# birth1_brd2.net
KiCad netlist of a schematic drawn in EAGLE
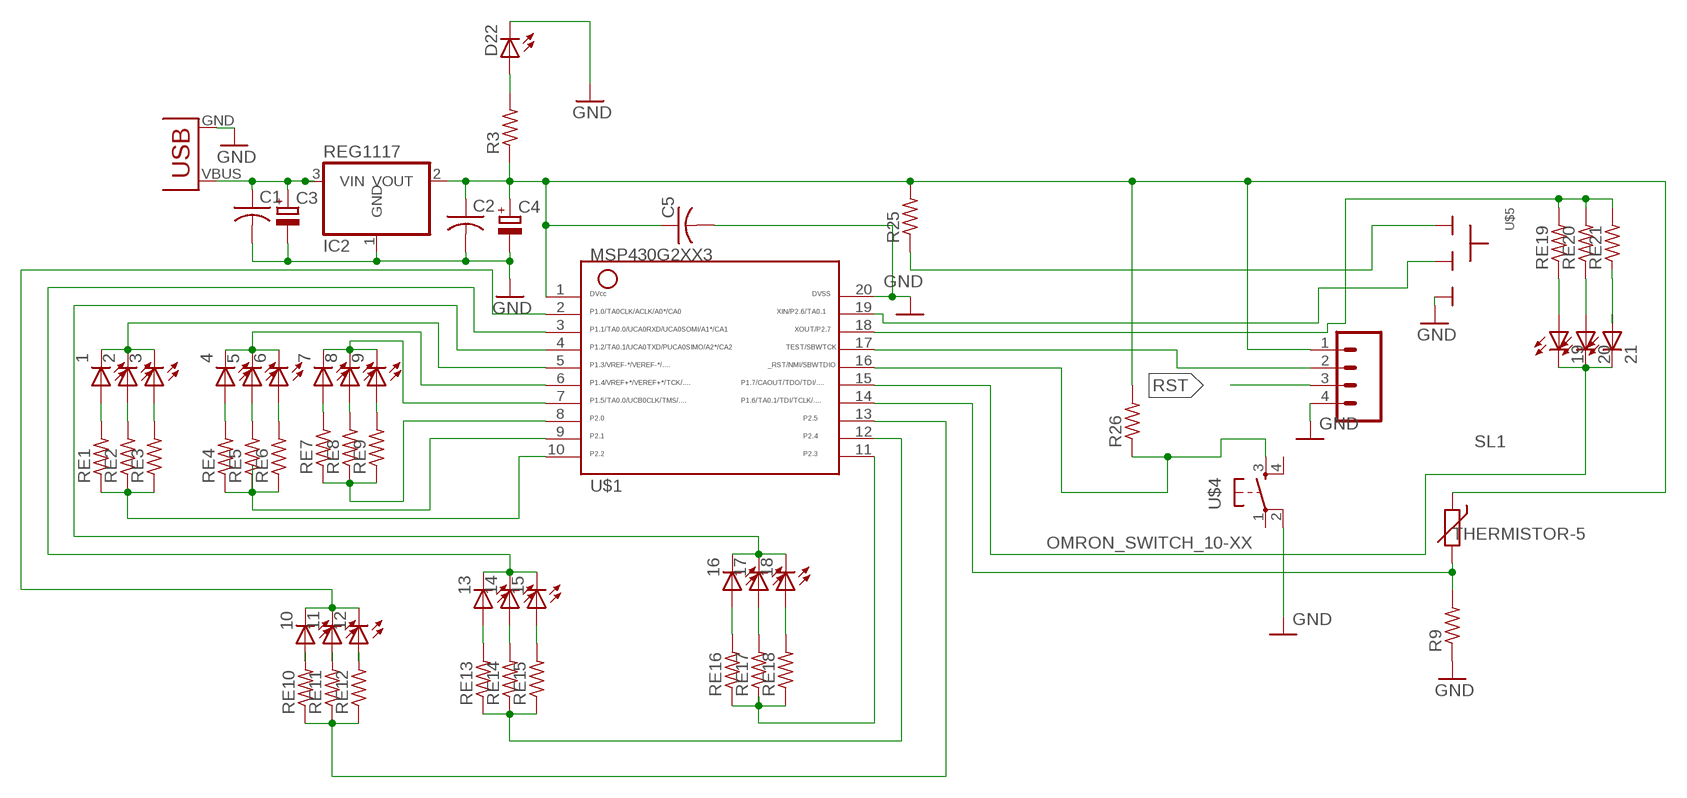
[diagram p0: schematic, sheet 1]

(export (version "E")
  (design (tool "Eeschema 10.0.6"))
  (components
    (comp (ref "1")
      (value "LED3MM")
      (footprint "eagle-import:LED3MM")
      (libsource (lib "eagle-import") (part "LED3MM"))
    )
    (comp (ref "2")
      (value "LED3MM")
      (footprint "eagle-import:LED3MM")
      (libsource (lib "eagle-import") (part "LED3MM"))
    )
    (comp (ref "3")
      (value "LED3MM")
      (footprint "eagle-import:LED3MM")
      (libsource (lib "eagle-import") (part "LED3MM"))
    )
    (comp (ref "4")
      (value "LED3MM")
      (footprint "eagle-import:LED3MM")
      (libsource (lib "eagle-import") (part "LED3MM"))
    )
    (comp (ref "5")
      (value "LED3MM")
      (footprint "eagle-import:LED3MM")
      (libsource (lib "eagle-import") (part "LED3MM"))
    )
    (comp (ref "6")
      (value "LED3MM")
      (footprint "eagle-import:LED3MM")
      (libsource (lib "eagle-import") (part "LED3MM"))
    )
    (comp (ref "7")
      (value "LED3MM")
      (footprint "eagle-import:LED3MM")
      (libsource (lib "eagle-import") (part "LED3MM"))
    )
    (comp (ref "8")
      (value "LED3MM")
      (footprint "eagle-import:LED3MM")
      (libsource (lib "eagle-import") (part "LED3MM"))
    )
    (comp (ref "9")
      (value "LED3MM")
      (footprint "eagle-import:LED3MM")
      (libsource (lib "eagle-import") (part "LED3MM"))
    )
    (comp (ref "10")
      (value "LED3MM")
      (footprint "eagle-import:LED3MM")
      (libsource (lib "eagle-import") (part "LED3MM"))
    )
    (comp (ref "11")
      (value "LED3MM")
      (footprint "eagle-import:LED3MM")
      (libsource (lib "eagle-import") (part "LED3MM"))
    )
    (comp (ref "12")
      (value "LED3MM")
      (footprint "eagle-import:LED3MM")
      (libsource (lib "eagle-import") (part "LED3MM"))
    )
    (comp (ref "13")
      (value "LED3MM")
      (footprint "eagle-import:LED3MM")
      (libsource (lib "eagle-import") (part "LED3MM"))
    )
    (comp (ref "14")
      (value "LED3MM")
      (footprint "eagle-import:LED3MM")
      (libsource (lib "eagle-import") (part "LED3MM"))
    )
    (comp (ref "15")
      (value "LED3MM")
      (footprint "eagle-import:LED3MM")
      (libsource (lib "eagle-import") (part "LED3MM"))
    )
    (comp (ref "16")
      (value "LED3MM")
      (footprint "eagle-import:LED3MM")
      (libsource (lib "eagle-import") (part "LED3MM"))
    )
    (comp (ref "17")
      (value "LED3MM")
      (footprint "eagle-import:LED3MM")
      (libsource (lib "eagle-import") (part "LED3MM"))
    )
    (comp (ref "18")
      (value "LED3MM")
      (footprint "eagle-import:LED3MM")
      (libsource (lib "eagle-import") (part "LED3MM"))
    )
    (comp (ref "19")
      (value "LED3MM")
      (footprint "eagle-import:LED3MM")
      (libsource (lib "eagle-import") (part "LED3MM"))
    )
    (comp (ref "20")
      (value "LED3MM")
      (footprint "eagle-import:LED3MM")
      (libsource (lib "eagle-import") (part "LED3MM"))
    )
    (comp (ref "21")
      (value "LED3MM")
      (footprint "eagle-import:LED3MM")
      (libsource (lib "eagle-import") (part "LED3MM"))
    )
    (comp (ref "C1")
      (value "C-US025-025X050")
      (footprint "eagle-import:C025-025X050")
      (libsource (lib "eagle-import") (part "C-US025-025X050"))
    )
    (comp (ref "C2")
      (value "C-US025-025X050")
      (footprint "eagle-import:C025-025X050")
      (libsource (lib "eagle-import") (part "C-US025-025X050"))
    )
    (comp (ref "C3")
      (value "CPOL-EUE2.5-7")
      (footprint "eagle-import:E2,5-7")
      (libsource (lib "eagle-import") (part "CPOL-EUE2.5-7"))
    )
    (comp (ref "C4")
      (value "CPOL-EUE2.5-7")
      (footprint "eagle-import:E2,5-7")
      (libsource (lib "eagle-import") (part "CPOL-EUE2.5-7"))
    )
    (comp (ref "C5")
      (value "C-US025-025X050")
      (footprint "eagle-import:C025-025X050")
      (libsource (lib "eagle-import") (part "C-US025-025X050"))
    )
    (comp (ref "D22")
      (value "LED3MM")
      (footprint "eagle-import:LED3MM")
      (libsource (lib "eagle-import") (part "LED3MM"))
    )
    (comp (ref "IC2")
      (value "REG1117")
      (footprint "eagle-import:SOT223")
      (libsource (lib "eagle-import") (part "REG1117"))
    )
    (comp (ref "R3")
      (value "R-US_0204/7")
      (footprint "eagle-import:0204_7")
      (libsource (lib "eagle-import") (part "R-US_0204/7"))
    )
    (comp (ref "R8")
      (value "THERMISTOR-5")
      (footprint "eagle-import:R-5")
      (libsource (lib "eagle-import") (part "THERMISTOR-5"))
    )
    (comp (ref "R9")
      (value "R-US_0204/7")
      (footprint "eagle-import:0204_7")
      (libsource (lib "eagle-import") (part "R-US_0204/7"))
    )
    (comp (ref "R25")
      (value "R-US_0204/7")
      (footprint "eagle-import:0204_7")
      (libsource (lib "eagle-import") (part "R-US_0204/7"))
    )
    (comp (ref "R26")
      (value "R-US_0204/7")
      (footprint "eagle-import:0204_7")
      (libsource (lib "eagle-import") (part "R-US_0204/7"))
    )
    (comp (ref "RE1")
      (value "R-US_0204/7")
      (footprint "eagle-import:0204_7")
      (libsource (lib "eagle-import") (part "R-US_0204/7"))
    )
    (comp (ref "RE2")
      (value "R-US_0204/7")
      (footprint "eagle-import:0204_7")
      (libsource (lib "eagle-import") (part "R-US_0204/7"))
    )
    (comp (ref "RE3")
      (value "R-US_0204/7")
      (footprint "eagle-import:0204_7")
      (libsource (lib "eagle-import") (part "R-US_0204/7"))
    )
    (comp (ref "RE4")
      (value "R-US_0204/7")
      (footprint "eagle-import:0204_7")
      (libsource (lib "eagle-import") (part "R-US_0204/7"))
    )
    (comp (ref "RE5")
      (value "R-US_0204/7")
      (footprint "eagle-import:0204_7")
      (libsource (lib "eagle-import") (part "R-US_0204/7"))
    )
    (comp (ref "RE6")
      (value "R-US_0204/7")
      (footprint "eagle-import:0204_7")
      (libsource (lib "eagle-import") (part "R-US_0204/7"))
    )
    (comp (ref "RE7")
      (value "R-US_0204/7")
      (footprint "eagle-import:0204_7")
      (libsource (lib "eagle-import") (part "R-US_0204/7"))
    )
    (comp (ref "RE8")
      (value "R-US_0204/7")
      (footprint "eagle-import:0204_7")
      (libsource (lib "eagle-import") (part "R-US_0204/7"))
    )
    (comp (ref "RE9")
      (value "R-US_0204/7")
      (footprint "eagle-import:0204_7")
      (libsource (lib "eagle-import") (part "R-US_0204/7"))
    )
    (comp (ref "RE10")
      (value "R-US_0204/7")
      (footprint "eagle-import:0204_7")
      (libsource (lib "eagle-import") (part "R-US_0204/7"))
    )
    (comp (ref "RE11")
      (value "R-US_0204/7")
      (footprint "eagle-import:0204_7")
      (libsource (lib "eagle-import") (part "R-US_0204/7"))
    )
    (comp (ref "RE12")
      (value "R-US_0204/7")
      (footprint "eagle-import:0204_7")
      (libsource (lib "eagle-import") (part "R-US_0204/7"))
    )
    (comp (ref "RE13")
      (value "R-US_0204/7")
      (footprint "eagle-import:0204_7")
      (libsource (lib "eagle-import") (part "R-US_0204/7"))
    )
    (comp (ref "RE14")
      (value "R-US_0204/7")
      (footprint "eagle-import:0204_7")
      (libsource (lib "eagle-import") (part "R-US_0204/7"))
    )
    (comp (ref "RE15")
      (value "R-US_0204/7")
      (footprint "eagle-import:0204_7")
      (libsource (lib "eagle-import") (part "R-US_0204/7"))
    )
    (comp (ref "RE16")
      (value "R-US_0204/7")
      (footprint "eagle-import:0204_7")
      (libsource (lib "eagle-import") (part "R-US_0204/7"))
    )
    (comp (ref "RE17")
      (value "R-US_0204/7")
      (footprint "eagle-import:0204_7")
      (libsource (lib "eagle-import") (part "R-US_0204/7"))
    )
    (comp (ref "RE18")
      (value "R-US_0204/7")
      (footprint "eagle-import:0204_7")
      (libsource (lib "eagle-import") (part "R-US_0204/7"))
    )
    (comp (ref "RE19")
      (value "R-US_0204/7")
      (footprint "eagle-import:0204_7")
      (libsource (lib "eagle-import") (part "R-US_0204/7"))
    )
    (comp (ref "RE20")
      (value "R-US_0204/7")
      (footprint "eagle-import:0204_7")
      (libsource (lib "eagle-import") (part "R-US_0204/7"))
    )
    (comp (ref "RE21")
      (value "R-US_0204/7")
      (footprint "eagle-import:0204_7")
      (libsource (lib "eagle-import") (part "R-US_0204/7"))
    )
    (comp (ref "SL1")
      (value "M04")
      (footprint "eagle-import:04P")
      (libsource (lib "eagle-import") (part "M04"))
    )
    (comp (ref "U$1")
      (value "MSP430G2553DIP20")
      (footprint "eagle-import:G2553-DIP20")
      (libsource (lib "eagle-import") (part "MSP430G2553DIP20"))
    )
    (comp (ref "U$2")
      (value "USB(POWER)")
      (footprint "eagle-import:USB(POWER)")
      (libsource (lib "eagle-import") (part "USB(POWER)"))
    )
    (comp (ref "U$4")
      (value "OMRON_SWITCH_10-XX")
      (footprint "eagle-import:B3F-10XX")
      (libsource (lib "eagle-import") (part "OMRON_SWITCH_10-XX"))
    )
    (comp (ref "U$5")
      (value "SLIDESWITCH-BIG")
      (footprint "eagle-import:BIGSWITCH")
      (libsource (lib "eagle-import") (part "SLIDESWITCH-BIG"))
    )
  )
  (nets
    (net (code "1") (name "GND") (class "Default")
      (node (ref "C1") (pin "2") (pinfunction "2_2") (pintype "passive"))
      (node (ref "C2") (pin "2") (pinfunction "2_2") (pintype "passive"))
      (node (ref "C3") (pin "-") (pinfunction "-_-") (pintype "passive"))
      (node (ref "C4") (pin "-") (pinfunction "-_-") (pintype "passive"))
      (node (ref "C5") (pin "2") (pinfunction "2_2") (pintype "passive"))
      (node (ref "D22") (pin "K") (pinfunction "C_K") (pintype "passive"))
      (node (ref "IC2") (pin "1") (pinfunction "GND_1") (pintype "power_in"))
      (node (ref "R9") (pin "1") (pinfunction "1_1") (pintype "passive"))
      (node (ref "SL1") (pin "4") (pinfunction "4_4") (pintype "passive"))
      (node (ref "U$1") (pin "20") (pinfunction "20_20") (pintype "power_in"))
      (node (ref "U$2") (pin "GND") (pinfunction "GND_GND") (pintype "power_in"))
      (node (ref "U$4") (pin "2") (pinfunction "P1_2") (pintype "passive"))
      (node (ref "U$5") (pin "3") (pinfunction "3_3") (pintype "bidirectional"))
    )
    (net (code "2") (name "Net-(1-C)") (class "Default")
      (node (ref "1") (pin "K") (pinfunction "C_K") (pintype "passive"))
      (node (ref "2") (pin "K") (pinfunction "C_K") (pintype "passive"))
      (node (ref "3") (pin "K") (pinfunction "C_K") (pintype "passive"))
      (node (ref "U$1") (pin "5") (pinfunction "5_5") (pintype "bidirectional"))
    )
    (net (code "3") (name "Net-(1-PadA)") (class "Default")
      (node (ref "1") (pin "A") (pinfunction "A_A") (pintype "passive"))
      (node (ref "RE1") (pin "2") (pinfunction "2_2") (pintype "passive"))
    )
    (net (code "4") (name "Net-(2-PadA)") (class "Default")
      (node (ref "2") (pin "A") (pinfunction "A_A") (pintype "passive"))
      (node (ref "RE2") (pin "2") (pinfunction "2_2") (pintype "passive"))
    )
    (net (code "5") (name "Net-(3-PadA)") (class "Default")
      (node (ref "3") (pin "A") (pinfunction "A_A") (pintype "passive"))
      (node (ref "RE3") (pin "2") (pinfunction "2_2") (pintype "passive"))
    )
    (net (code "6") (name "Net-(4-C)") (class "Default")
      (node (ref "4") (pin "K") (pinfunction "C_K") (pintype "passive"))
      (node (ref "5") (pin "K") (pinfunction "C_K") (pintype "passive"))
      (node (ref "6") (pin "K") (pinfunction "C_K") (pintype "passive"))
      (node (ref "U$1") (pin "6") (pinfunction "6_6") (pintype "bidirectional"))
    )
    (net (code "7") (name "Net-(4-PadA)") (class "Default")
      (node (ref "4") (pin "A") (pinfunction "A_A") (pintype "passive"))
      (node (ref "RE4") (pin "2") (pinfunction "2_2") (pintype "passive"))
    )
    (net (code "8") (name "Net-(5-PadA)") (class "Default")
      (node (ref "5") (pin "A") (pinfunction "A_A") (pintype "passive"))
      (node (ref "RE5") (pin "2") (pinfunction "2_2") (pintype "passive"))
    )
    (net (code "9") (name "Net-(6-PadA)") (class "Default")
      (node (ref "6") (pin "A") (pinfunction "A_A") (pintype "passive"))
      (node (ref "RE6") (pin "2") (pinfunction "2_2") (pintype "passive"))
    )
    (net (code "10") (name "Net-(7-C)") (class "Default")
      (node (ref "7") (pin "K") (pinfunction "C_K") (pintype "passive"))
      (node (ref "8") (pin "K") (pinfunction "C_K") (pintype "passive"))
      (node (ref "9") (pin "K") (pinfunction "C_K") (pintype "passive"))
      (node (ref "U$1") (pin "7") (pinfunction "7_7") (pintype "bidirectional"))
    )
    (net (code "11") (name "Net-(7-PadA)") (class "Default")
      (node (ref "7") (pin "A") (pinfunction "A_A") (pintype "passive"))
      (node (ref "RE7") (pin "2") (pinfunction "2_2") (pintype "passive"))
    )
    (net (code "12") (name "Net-(8-PadA)") (class "Default")
      (node (ref "8") (pin "A") (pinfunction "A_A") (pintype "passive"))
      (node (ref "RE8") (pin "2") (pinfunction "2_2") (pintype "passive"))
    )
    (net (code "13") (name "Net-(9-PadA)") (class "Default")
      (node (ref "9") (pin "A") (pinfunction "A_A") (pintype "passive"))
      (node (ref "RE9") (pin "2") (pinfunction "2_2") (pintype "passive"))
    )
    (net (code "14") (name "Net-(10-C)") (class "Default")
      (node (ref "10") (pin "K") (pinfunction "C_K") (pintype "passive"))
      (node (ref "11") (pin "K") (pinfunction "C_K") (pintype "passive"))
      (node (ref "12") (pin "K") (pinfunction "C_K") (pintype "passive"))
      (node (ref "U$1") (pin "2") (pinfunction "2_2") (pintype "bidirectional"))
    )
    (net (code "15") (name "Net-(10-PadA)") (class "Default")
      (node (ref "10") (pin "A") (pinfunction "A_A") (pintype "passive"))
      (node (ref "RE10") (pin "2") (pinfunction "2_2") (pintype "passive"))
    )
    (net (code "16") (name "Net-(11-PadA)") (class "Default")
      (node (ref "11") (pin "A") (pinfunction "A_A") (pintype "passive"))
      (node (ref "RE11") (pin "2") (pinfunction "2_2") (pintype "passive"))
    )
    (net (code "17") (name "Net-(12-PadA)") (class "Default")
      (node (ref "12") (pin "A") (pinfunction "A_A") (pintype "passive"))
      (node (ref "RE12") (pin "2") (pinfunction "2_2") (pintype "passive"))
    )
    (net (code "18") (name "Net-(13-C)") (class "Default")
      (node (ref "13") (pin "K") (pinfunction "C_K") (pintype "passive"))
      (node (ref "14") (pin "K") (pinfunction "C_K") (pintype "passive"))
      (node (ref "15") (pin "K") (pinfunction "C_K") (pintype "passive"))
      (node (ref "U$1") (pin "3") (pinfunction "3_3") (pintype "bidirectional"))
    )
    (net (code "19") (name "Net-(13-PadA)") (class "Default")
      (node (ref "13") (pin "A") (pinfunction "A_A") (pintype "passive"))
      (node (ref "RE13") (pin "2") (pinfunction "2_2") (pintype "passive"))
    )
    (net (code "20") (name "Net-(14-PadA)") (class "Default")
      (node (ref "14") (pin "A") (pinfunction "A_A") (pintype "passive"))
      (node (ref "RE14") (pin "2") (pinfunction "2_2") (pintype "passive"))
    )
    (net (code "21") (name "Net-(15-PadA)") (class "Default")
      (node (ref "15") (pin "A") (pinfunction "A_A") (pintype "passive"))
      (node (ref "RE15") (pin "2") (pinfunction "2_2") (pintype "passive"))
    )
    (net (code "22") (name "Net-(16-C)") (class "Default")
      (node (ref "16") (pin "K") (pinfunction "C_K") (pintype "passive"))
      (node (ref "17") (pin "K") (pinfunction "C_K") (pintype "passive"))
      (node (ref "18") (pin "K") (pinfunction "C_K") (pintype "passive"))
      (node (ref "U$1") (pin "4") (pinfunction "4_4") (pintype "bidirectional"))
    )
    (net (code "23") (name "Net-(16-PadA)") (class "Default")
      (node (ref "16") (pin "A") (pinfunction "A_A") (pintype "passive"))
      (node (ref "RE16") (pin "2") (pinfunction "2_2") (pintype "passive"))
    )
    (net (code "24") (name "Net-(17-PadA)") (class "Default")
      (node (ref "17") (pin "A") (pinfunction "A_A") (pintype "passive"))
      (node (ref "RE17") (pin "2") (pinfunction "2_2") (pintype "passive"))
    )
    (net (code "25") (name "Net-(18-PadA)") (class "Default")
      (node (ref "18") (pin "A") (pinfunction "A_A") (pintype "passive"))
      (node (ref "RE18") (pin "2") (pinfunction "2_2") (pintype "passive"))
    )
    (net (code "26") (name "Net-(19-C)") (class "Default")
      (node (ref "19") (pin "K") (pinfunction "C_K") (pintype "passive"))
      (node (ref "20") (pin "K") (pinfunction "C_K") (pintype "passive"))
      (node (ref "21") (pin "K") (pinfunction "C_K") (pintype "passive"))
      (node (ref "U$1") (pin "15") (pinfunction "15_15") (pintype "bidirectional"))
    )
    (net (code "27") (name "Net-(19-PadA)") (class "Default")
      (node (ref "19") (pin "A") (pinfunction "A_A") (pintype "passive"))
      (node (ref "RE19") (pin "1") (pinfunction "1_1") (pintype "passive"))
    )
    (net (code "28") (name "Net-(20-PadA)") (class "Default")
      (node (ref "20") (pin "A") (pinfunction "A_A") (pintype "passive"))
      (node (ref "RE20") (pin "1") (pinfunction "1_1") (pintype "passive"))
    )
    (net (code "29") (name "Net-(21-PadA)") (class "Default")
      (node (ref "21") (pin "A") (pinfunction "A_A") (pintype "passive"))
      (node (ref "RE21") (pin "1") (pinfunction "1_1") (pintype "passive"))
    )
    (net (code "30") (name "Net-(D22-PadA)") (class "Default")
      (node (ref "D22") (pin "A") (pinfunction "A_A") (pintype "passive"))
      (node (ref "R3") (pin "2") (pinfunction "2_2") (pintype "passive"))
    )
    (net (code "31") (name "Net-(IC2-VIN)") (class "Default")
      (node (ref "C1") (pin "1") (pinfunction "1_1") (pintype "passive"))
      (node (ref "C3") (pin "+") (pinfunction "+_+") (pintype "passive"))
      (node (ref "IC2") (pin "3") (pinfunction "VIN_3") (pintype "input"))
      (node (ref "U$2") (pin "VBUS") (pinfunction "VCC_VBUS") (pintype "power_in"))
    )
    (net (code "32") (name "Net-(IC2-VOUT)") (class "Default")
      (node (ref "C2") (pin "1") (pinfunction "1_1") (pintype "passive"))
      (node (ref "C4") (pin "+") (pinfunction "+_+") (pintype "passive"))
      (node (ref "C5") (pin "1") (pinfunction "1_1") (pintype "passive"))
      (node (ref "IC2") (pin "2") (pinfunction "VOUT_2") (pintype "output"))
      (node (ref "R25") (pin "2") (pinfunction "2_2") (pintype "passive"))
      (node (ref "R26") (pin "2") (pinfunction "2_2") (pintype "passive"))
      (node (ref "R3") (pin "1") (pinfunction "1_1") (pintype "passive"))
      (node (ref "R8") (pin "1") (pinfunction "1_1") (pintype "passive"))
      (node (ref "SL1") (pin "1") (pinfunction "1_1") (pintype "passive"))
      (node (ref "U$1") (pin "1") (pinfunction "1_1") (pintype "power_in"))
    )
    (net (code "33") (name "Net-(R8-Pad2)") (class "Default")
      (node (ref "R8") (pin "2") (pinfunction "2_2") (pintype "passive"))
      (node (ref "R9") (pin "2") (pinfunction "2_2") (pintype "passive"))
      (node (ref "U$1") (pin "14") (pinfunction "14_14") (pintype "bidirectional"))
    )
    (net (code "34") (name "Net-(R25-Pad1)") (class "Default")
      (node (ref "R25") (pin "1") (pinfunction "1_1") (pintype "passive"))
      (node (ref "U$5") (pin "1") (pinfunction "1_1") (pintype "bidirectional"))
    )
    (net (code "35") (name "Net-(RE1-Pad1)") (class "Default")
      (node (ref "RE1") (pin "1") (pinfunction "1_1") (pintype "passive"))
      (node (ref "RE2") (pin "1") (pinfunction "1_1") (pintype "passive"))
      (node (ref "RE3") (pin "1") (pinfunction "1_1") (pintype "passive"))
      (node (ref "U$1") (pin "10") (pinfunction "10_10") (pintype "bidirectional"))
    )
    (net (code "36") (name "Net-(RE4-Pad1)") (class "Default")
      (node (ref "RE4") (pin "1") (pinfunction "1_1") (pintype "passive"))
      (node (ref "RE5") (pin "1") (pinfunction "1_1") (pintype "passive"))
      (node (ref "RE6") (pin "1") (pinfunction "1_1") (pintype "passive"))
      (node (ref "U$1") (pin "9") (pinfunction "9_9") (pintype "bidirectional"))
    )
    (net (code "37") (name "Net-(RE7-Pad1)") (class "Default")
      (node (ref "RE7") (pin "1") (pinfunction "1_1") (pintype "passive"))
      (node (ref "RE8") (pin "1") (pinfunction "1_1") (pintype "passive"))
      (node (ref "RE9") (pin "1") (pinfunction "1_1") (pintype "passive"))
      (node (ref "U$1") (pin "8") (pinfunction "8_8") (pintype "bidirectional"))
    )
    (net (code "38") (name "Net-(RE10-Pad1)") (class "Default")
      (node (ref "RE10") (pin "1") (pinfunction "1_1") (pintype "passive"))
      (node (ref "RE11") (pin "1") (pinfunction "1_1") (pintype "passive"))
      (node (ref "RE12") (pin "1") (pinfunction "1_1") (pintype "passive"))
      (node (ref "U$1") (pin "13") (pinfunction "13_13") (pintype "bidirectional"))
    )
    (net (code "39") (name "Net-(RE13-Pad1)") (class "Default")
      (node (ref "RE13") (pin "1") (pinfunction "1_1") (pintype "passive"))
      (node (ref "RE14") (pin "1") (pinfunction "1_1") (pintype "passive"))
      (node (ref "RE15") (pin "1") (pinfunction "1_1") (pintype "passive"))
      (node (ref "U$1") (pin "12") (pinfunction "12_12") (pintype "bidirectional"))
    )
    (net (code "40") (name "Net-(RE16-Pad1)") (class "Default")
      (node (ref "RE16") (pin "1") (pinfunction "1_1") (pintype "passive"))
      (node (ref "RE17") (pin "1") (pinfunction "1_1") (pintype "passive"))
      (node (ref "RE18") (pin "1") (pinfunction "1_1") (pintype "passive"))
      (node (ref "U$1") (pin "11") (pinfunction "11_11") (pintype "bidirectional"))
    )
    (net (code "41") (name "Net-(RE19-Pad2)") (class "Default")
      (node (ref "RE19") (pin "2") (pinfunction "2_2") (pintype "passive"))
      (node (ref "RE20") (pin "2") (pinfunction "2_2") (pintype "passive"))
      (node (ref "RE21") (pin "2") (pinfunction "2_2") (pintype "passive"))
      (node (ref "U$1") (pin "18") (pinfunction "18_18") (pintype "bidirectional"))
    )
    (net (code "42") (name "Net-(SL1-Pad2)") (class "Default")
      (node (ref "SL1") (pin "2") (pinfunction "2_2") (pintype "passive"))
      (node (ref "U$1") (pin "17") (pinfunction "17_17") (pintype "bidirectional"))
    )
    (net (code "43") (name "Net-(U$1-Pad19)") (class "Default")
      (node (ref "U$1") (pin "19") (pinfunction "19_19") (pintype "bidirectional"))
      (node (ref "U$5") (pin "2") (pinfunction "2_2") (pintype "bidirectional"))
    )
    (net (code "44") (name "RST") (class "Default")
      (node (ref "R26") (pin "1") (pinfunction "1_1") (pintype "passive"))
      (node (ref "SL1") (pin "3") (pinfunction "3_3") (pintype "passive"))
      (node (ref "U$1") (pin "16") (pinfunction "16_16") (pintype "bidirectional"))
      (node (ref "U$4") (pin "3") (pinfunction "S_3") (pintype "passive"))
    )
    (net (code "45") (name "unconnected-(U$4-P-Pad1)") (class "Default")
      (node (ref "U$4") (pin "1") (pinfunction "P_1") (pintype "passive"))
    )
    (net (code "46") (name "unconnected-(U$4-S1-Pad4)") (class "Default")
      (node (ref "U$4") (pin "4") (pinfunction "S1_4") (pintype "passive"))
    )
  )
)
